# uc4h_airspeed_v020-wholes.net
KiCad netlist of a schematic drawn in EAGLE
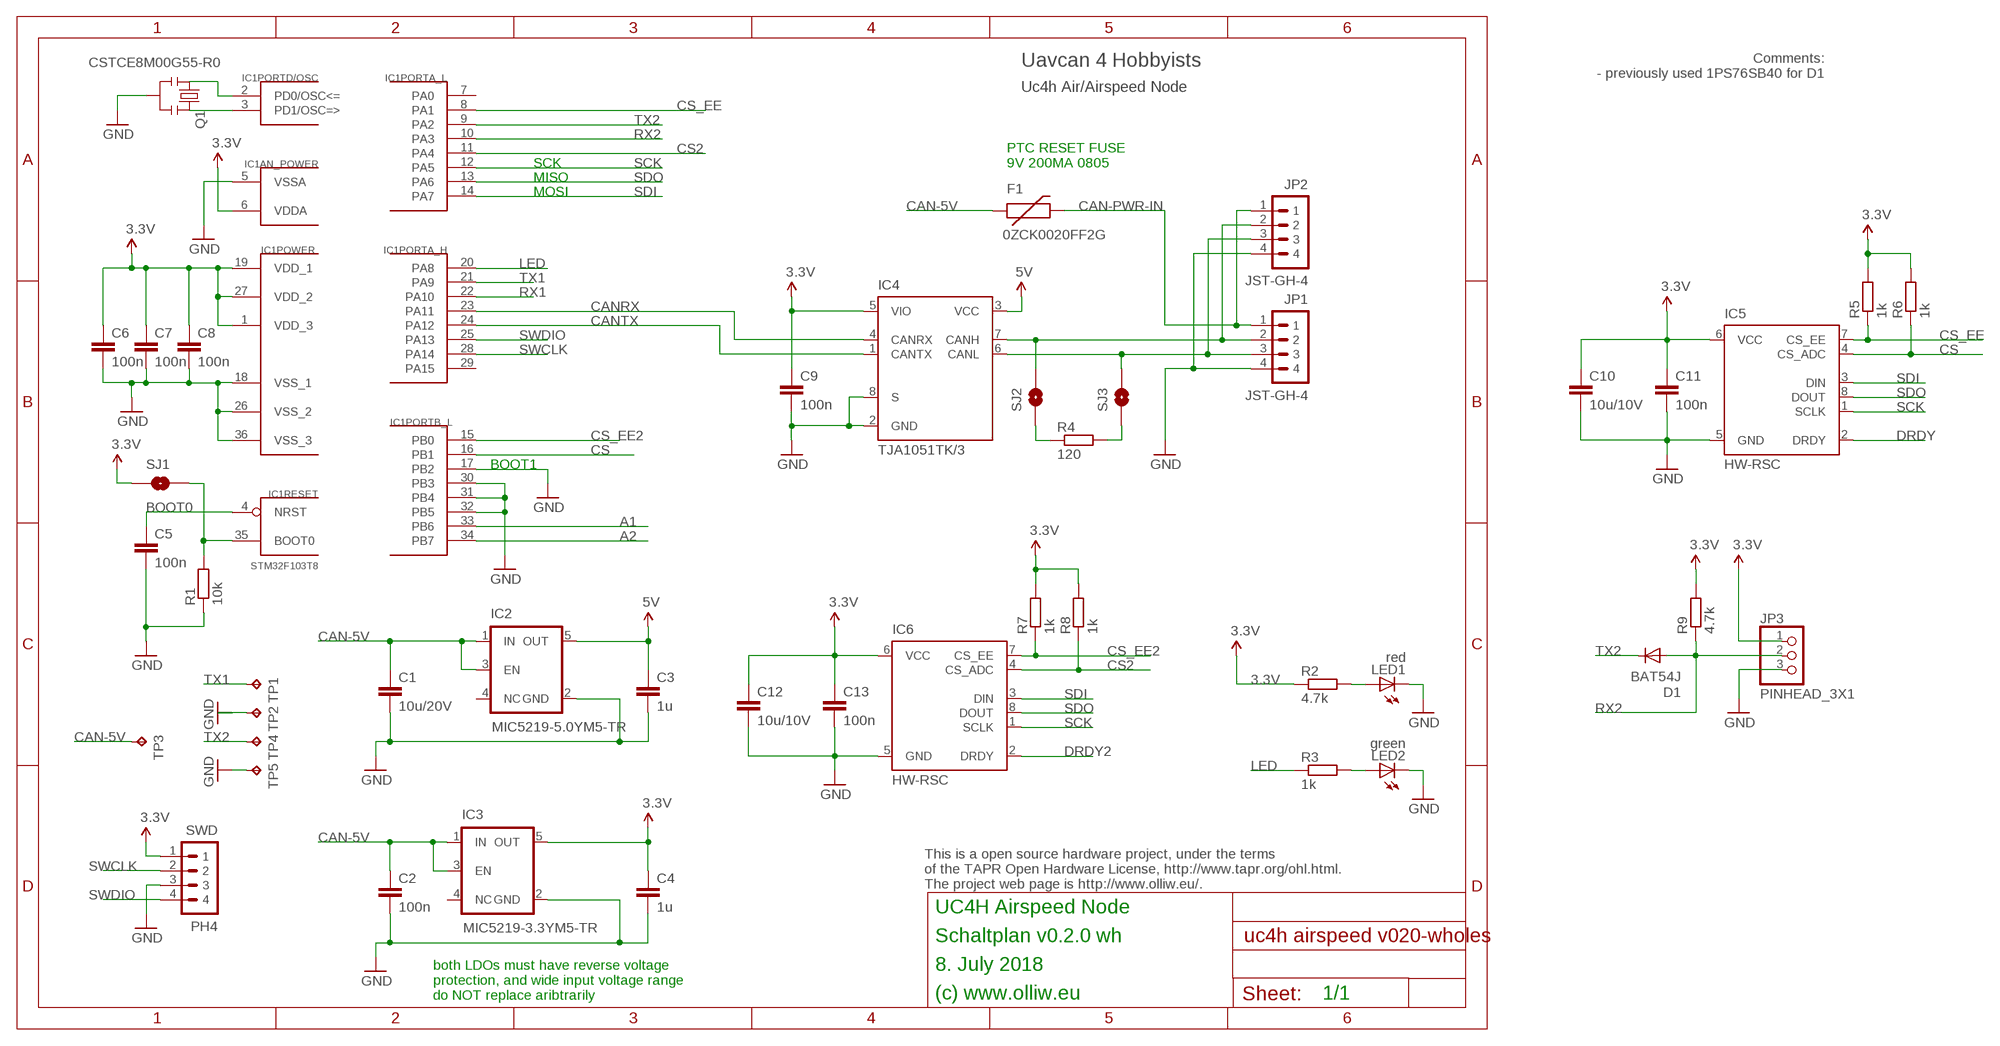
[diagram p0: schematic, sheet 1]

(export (version "E")
  (design (tool "Eeschema 10.0.6"))
  (components
    (comp (ref "C1")
      (value "10u/20V")
      (footprint "eagle-import:C1206")
      (libsource (lib "eagle-import") (part "C-EUC1206"))
    )
    (comp (ref "C2")
      (value "100n")
      (footprint "eagle-import:C0603K")
      (libsource (lib "eagle-import") (part "C-EUC0603K"))
    )
    (comp (ref "C3")
      (value "1u")
      (footprint "eagle-import:C0603K")
      (libsource (lib "eagle-import") (part "C-EUC0603K"))
    )
    (comp (ref "C4")
      (value "1u")
      (footprint "eagle-import:C0603K")
      (libsource (lib "eagle-import") (part "C-EUC0603K"))
    )
    (comp (ref "C5")
      (value "100n")
      (footprint "eagle-import:C0603K")
      (libsource (lib "eagle-import") (part "C-EUC0603K"))
    )
    (comp (ref "C6")
      (value "100n")
      (footprint "eagle-import:C0603K")
      (libsource (lib "eagle-import") (part "C-EUC0603K"))
    )
    (comp (ref "C7")
      (value "100n")
      (footprint "eagle-import:C0603K")
      (libsource (lib "eagle-import") (part "C-EUC0603K"))
    )
    (comp (ref "C8")
      (value "100n")
      (footprint "eagle-import:C0603K")
      (libsource (lib "eagle-import") (part "C-EUC0603K"))
    )
    (comp (ref "C9")
      (value "100n")
      (footprint "eagle-import:C0603K")
      (libsource (lib "eagle-import") (part "C-EUC0603K"))
    )
    (comp (ref "C10")
      (value "10u/10V")
      (footprint "eagle-import:C1206")
      (libsource (lib "eagle-import") (part "C-EUC1206"))
    )
    (comp (ref "C11")
      (value "100n")
      (footprint "eagle-import:C0603K")
      (libsource (lib "eagle-import") (part "C-EUC0603K"))
    )
    (comp (ref "C12")
      (value "10u/10V")
      (footprint "eagle-import:C1206")
      (libsource (lib "eagle-import") (part "C-EUC1206"))
    )
    (comp (ref "C13")
      (value "100n")
      (footprint "eagle-import:C0603K")
      (libsource (lib "eagle-import") (part "C-EUC0603K"))
    )
    (comp (ref "D1")
      (value "BAT54J")
      (footprint "eagle-import:SOD110-R")
      (libsource (lib "eagle-import") (part "DIODE-SOD110-R"))
    )
    (comp (ref "F1")
      (value "0ZCK0020FF2G")
      (footprint "eagle-import:FUSE-0805")
      (libsource (lib "eagle-import") (part "FUSE-PTCFUSE-0805"))
    )
    (comp (ref "IC1")
      (value "STM32F103T8")
      (footprint "eagle-import:VFQFPN36")
      (libsource (lib "eagle-import") (part "STM32F10XTXU6"))
    )
    (comp (ref "IC2")
      (value "MIC5219-5.0YM5-TR")
      (footprint "eagle-import:SOT23-5")
      (libsource (lib "eagle-import") (part "V_REG_TPS76433SOT23-5"))
    )
    (comp (ref "IC3")
      (value "MIC5219-3.3YM5-TR")
      (footprint "eagle-import:SOT23-5")
      (libsource (lib "eagle-import") (part "V_REG_TPS76433SOT23-5"))
    )
    (comp (ref "IC4")
      (value "TJA1051TK/3")
      (footprint "eagle-import:HVSON8")
      (libsource (lib "eagle-import") (part "TJA1051TK/3"))
    )
    (comp (ref "IC5")
      (value "HW-RSC")
      (footprint "eagle-import:HONEYWELL-8")
      (libsource (lib "eagle-import") (part "HW-RSC"))
    )
    (comp (ref "IC6")
      (value "HW-RSC")
      (footprint "eagle-import:HONEYWELL-8")
      (libsource (lib "eagle-import") (part "HW-RSC"))
    )
    (comp (ref "JP1")
      (value "JST-GH-4")
      (footprint "eagle-import:SM04B-GHS-TB")
      (libsource (lib "eagle-import") (part "JST-GH-4"))
    )
    (comp (ref "JP2")
      (value "JST-GH-4")
      (footprint "eagle-import:SM04B-GHS-TB")
      (libsource (lib "eagle-import") (part "JST-GH-4"))
    )
    (comp (ref "JP3")
      (value "PINHEAD_3X1")
      (footprint "eagle-import:PINHEAD_3X1")
      (libsource (lib "eagle-import") (part "PINHEAD_3X1"))
    )
    (comp (ref "LED1")
      (value "red")
      (footprint "eagle-import:CHIPLED_0603")
      (libsource (lib "eagle-import") (part "LEDCHIPLED_0603"))
    )
    (comp (ref "LED2")
      (value "green")
      (footprint "eagle-import:CHIPLED_0603")
      (libsource (lib "eagle-import") (part "LEDCHIPLED_0603"))
    )
    (comp (ref "Q1")
      (value "CSTCE8M00G55-R0")
      (footprint "eagle-import:RESONATOR-SMD")
      (libsource (lib "eagle-import") (part "RESONATORSMD"))
    )
    (comp (ref "R1")
      (value "10k")
      (footprint "eagle-import:R0603")
      (libsource (lib "eagle-import") (part "R-EU_R0603"))
    )
    (comp (ref "R2")
      (value "4.7k")
      (footprint "eagle-import:R0603")
      (libsource (lib "eagle-import") (part "R-EU_R0603"))
    )
    (comp (ref "R3")
      (value "1k")
      (footprint "eagle-import:R0603")
      (libsource (lib "eagle-import") (part "R-EU_R0603"))
    )
    (comp (ref "R4")
      (value "120")
      (footprint "eagle-import:R0603")
      (libsource (lib "eagle-import") (part "R-EU_R0603"))
    )
    (comp (ref "R5")
      (value "1k")
      (footprint "eagle-import:R0603")
      (libsource (lib "eagle-import") (part "R-EU_R0603"))
    )
    (comp (ref "R6")
      (value "1k")
      (footprint "eagle-import:R0603")
      (libsource (lib "eagle-import") (part "R-EU_R0603"))
    )
    (comp (ref "R7")
      (value "1k")
      (footprint "eagle-import:R0603")
      (libsource (lib "eagle-import") (part "R-EU_R0603"))
    )
    (comp (ref "R8")
      (value "1k")
      (footprint "eagle-import:R0603")
      (libsource (lib "eagle-import") (part "R-EU_R0603"))
    )
    (comp (ref "R9")
      (value "4.7k")
      (footprint "eagle-import:R0603")
      (libsource (lib "eagle-import") (part "R-EU_R0603"))
    )
    (comp (ref "SJ1")
      (value "BOOT0")
      (footprint "eagle-import:SJ_2S-NO")
      (libsource (lib "eagle-import") (part "SOLDERJUMPERNO"))
    )
    (comp (ref "SJ2")
      (value "SOLDERJUMPERNO")
      (footprint "eagle-import:SJ_2S-NO")
      (libsource (lib "eagle-import") (part "SOLDERJUMPERNO"))
    )
    (comp (ref "SJ3")
      (value "SOLDERJUMPERNO")
      (footprint "eagle-import:SJ_2S-NO")
      (libsource (lib "eagle-import") (part "SOLDERJUMPERNO"))
    )
    (comp (ref "SWD")
      (value "PH4")
      (footprint "eagle-import:4X1_1P27_OCT_BILEX")
      (libsource (lib "eagle-import") (part "P4X1_1P27-OCT_BILEX"))
    )
    (comp (ref "TP1")
      (value "TPB1,27")
      (footprint "eagle-import:B1,27")
      (libsource (lib "eagle-import") (part "TPB1,27"))
    )
    (comp (ref "TP2")
      (value "TPB1,27")
      (footprint "eagle-import:B1,27")
      (libsource (lib "eagle-import") (part "TPB1,27"))
    )
    (comp (ref "TP3")
      (value "TPB1,27")
      (footprint "eagle-import:B1,27")
      (libsource (lib "eagle-import") (part "TPB1,27"))
    )
    (comp (ref "TP4")
      (value "TPB1,27")
      (footprint "eagle-import:B1,27")
      (libsource (lib "eagle-import") (part "TPB1,27"))
    )
    (comp (ref "TP5")
      (value "TPB1,27")
      (footprint "eagle-import:B1,27")
      (libsource (lib "eagle-import") (part "TPB1,27"))
    )
  )
  (nets
    (net (code "1") (name "/A1") (class "Default")
      (node (ref "IC1") (pin "33") (pinfunction "PB6_33") (pintype "bidirectional"))
    )
    (net (code "2") (name "/A2") (class "Default")
      (node (ref "IC1") (pin "34") (pinfunction "PB7_34") (pintype "bidirectional"))
    )
    (net (code "3") (name "/CAN-5V") (class "Default")
      (node (ref "C1") (pin "1") (pinfunction "1_1") (pintype "passive"))
      (node (ref "C2") (pin "1") (pinfunction "1_1") (pintype "passive"))
      (node (ref "F1") (pin "1") (pinfunction "1_1") (pintype "bidirectional"))
      (node (ref "IC2") (pin "1") (pinfunction "IN_1") (pintype "power_in"))
      (node (ref "IC2") (pin "3") (pinfunction "EN_3") (pintype "input"))
      (node (ref "IC3") (pin "1") (pinfunction "IN_1") (pintype "power_in"))
      (node (ref "IC3") (pin "3") (pinfunction "EN_3") (pintype "input"))
      (node (ref "TP3") (pin "TP") (pinfunction "TP_TP") (pintype "input"))
    )
    (net (code "4") (name "/CAN-PWR-IN") (class "Default")
      (node (ref "F1") (pin "2") (pinfunction "2_2") (pintype "bidirectional"))
      (node (ref "JP1") (pin "1") (pinfunction "1_1") (pintype "passive"))
      (node (ref "JP2") (pin "1") (pinfunction "1_1") (pintype "passive"))
    )
    (net (code "5") (name "/CANRX") (class "Default")
      (node (ref "IC1") (pin "23") (pinfunction "PA11_23") (pintype "bidirectional"))
      (node (ref "IC4") (pin "4") (pinfunction "CANRX_4") (pintype "output"))
    )
    (net (code "6") (name "/CANTX") (class "Default")
      (node (ref "IC1") (pin "24") (pinfunction "PA12_24") (pintype "bidirectional"))
      (node (ref "IC4") (pin "1") (pinfunction "CANTX_1") (pintype "input"))
    )
    (net (code "7") (name "/CS") (class "Default")
      (node (ref "IC1") (pin "16") (pinfunction "PB1_16") (pintype "bidirectional"))
      (node (ref "IC5") (pin "4") (pinfunction "CS_ADC_4") (pintype "input"))
      (node (ref "R6") (pin "1") (pinfunction "1_1") (pintype "passive"))
    )
    (net (code "8") (name "/CS2") (class "Default")
      (node (ref "IC1") (pin "11") (pinfunction "PA4_11") (pintype "bidirectional"))
      (node (ref "IC6") (pin "4") (pinfunction "CS_ADC_4") (pintype "input"))
      (node (ref "R8") (pin "1") (pinfunction "1_1") (pintype "passive"))
    )
    (net (code "9") (name "/CS_EE") (class "Default")
      (node (ref "IC1") (pin "8") (pinfunction "PA1_8") (pintype "bidirectional"))
      (node (ref "IC5") (pin "7") (pinfunction "CS_EE_7") (pintype "input"))
      (node (ref "R5") (pin "1") (pinfunction "1_1") (pintype "passive"))
    )
    (net (code "10") (name "/CS_EE2") (class "Default")
      (node (ref "IC1") (pin "15") (pinfunction "PB0_15") (pintype "bidirectional"))
      (node (ref "IC6") (pin "7") (pinfunction "CS_EE_7") (pintype "input"))
      (node (ref "R7") (pin "1") (pinfunction "1_1") (pintype "passive"))
    )
    (net (code "11") (name "/DRDY") (class "Default")
      (node (ref "IC5") (pin "2") (pinfunction "DRDY_2") (pintype "output"))
    )
    (net (code "12") (name "/DRDY2") (class "Default")
      (node (ref "IC6") (pin "2") (pinfunction "DRDY_2") (pintype "output"))
    )
    (net (code "13") (name "/LED") (class "Default")
      (node (ref "IC1") (pin "20") (pinfunction "PA8_20") (pintype "bidirectional"))
      (node (ref "R3") (pin "1") (pinfunction "1_1") (pintype "passive"))
    )
    (net (code "14") (name "/RX1") (class "Default")
      (node (ref "IC1") (pin "22") (pinfunction "PA10_22") (pintype "bidirectional"))
    )
    (net (code "15") (name "/RX2") (class "Default")
      (node (ref "D1") (pin "A") (pinfunction "A_A") (pintype "passive"))
      (node (ref "IC1") (pin "10") (pinfunction "PA3_10") (pintype "bidirectional"))
      (node (ref "JP3") (pin "2") (pinfunction "3_2") (pintype "passive"))
      (node (ref "R9") (pin "1") (pinfunction "1_1") (pintype "passive"))
    )
    (net (code "16") (name "/SCK") (class "Default")
      (node (ref "IC1") (pin "12") (pinfunction "PA5_12") (pintype "bidirectional"))
      (node (ref "IC5") (pin "1") (pinfunction "SCLK_1") (pintype "input"))
      (node (ref "IC6") (pin "1") (pinfunction "SCLK_1") (pintype "input"))
    )
    (net (code "17") (name "/SDI") (class "Default")
      (node (ref "IC1") (pin "14") (pinfunction "PA7_14") (pintype "bidirectional"))
      (node (ref "IC5") (pin "3") (pinfunction "DIN_3") (pintype "input"))
      (node (ref "IC6") (pin "3") (pinfunction "DIN_3") (pintype "input"))
    )
    (net (code "18") (name "/SDO") (class "Default")
      (node (ref "IC1") (pin "13") (pinfunction "PA6_13") (pintype "bidirectional"))
      (node (ref "IC5") (pin "8") (pinfunction "DOUT_8") (pintype "output"))
      (node (ref "IC6") (pin "8") (pinfunction "DOUT_8") (pintype "output"))
    )
    (net (code "19") (name "/SWCLK") (class "Default")
      (node (ref "IC1") (pin "28") (pinfunction "PA14_28") (pintype "bidirectional"))
      (node (ref "SWD") (pin "2") (pinfunction "2_2") (pintype "passive"))
    )
    (net (code "20") (name "/SWDIO") (class "Default")
      (node (ref "IC1") (pin "25") (pinfunction "PA13_25") (pintype "bidirectional"))
      (node (ref "SWD") (pin "4") (pinfunction "4_4") (pintype "passive"))
    )
    (net (code "21") (name "/TX1") (class "Default")
      (node (ref "IC1") (pin "21") (pinfunction "PA9_21") (pintype "bidirectional"))
      (node (ref "TP1") (pin "TP") (pinfunction "TP_TP") (pintype "input"))
    )
    (net (code "22") (name "/TX2") (class "Default")
      (node (ref "D1") (pin "C") (pinfunction "C_C") (pintype "passive"))
      (node (ref "IC1") (pin "9") (pinfunction "PA2_9") (pintype "bidirectional"))
      (node (ref "TP4") (pin "TP") (pinfunction "TP_TP") (pintype "input"))
    )
    (net (code "23") (name "3.3V") (class "Default")
      (node (ref "C10") (pin "1") (pinfunction "1_1") (pintype "passive"))
      (node (ref "C11") (pin "1") (pinfunction "1_1") (pintype "passive"))
      (node (ref "C12") (pin "1") (pinfunction "1_1") (pintype "passive"))
      (node (ref "C13") (pin "1") (pinfunction "1_1") (pintype "passive"))
      (node (ref "C4") (pin "1") (pinfunction "1_1") (pintype "passive"))
      (node (ref "C6") (pin "1") (pinfunction "1_1") (pintype "passive"))
      (node (ref "C7") (pin "1") (pinfunction "1_1") (pintype "passive"))
      (node (ref "C8") (pin "1") (pinfunction "1_1") (pintype "passive"))
      (node (ref "C9") (pin "1") (pinfunction "1_1") (pintype "passive"))
      (node (ref "IC1") (pin "1") (pinfunction "VDD_3_1") (pintype "power_in"))
      (node (ref "IC1") (pin "19") (pinfunction "VDD_1_19") (pintype "power_in"))
      (node (ref "IC1") (pin "27") (pinfunction "VDD_2_27") (pintype "power_in"))
      (node (ref "IC1") (pin "6") (pinfunction "VDDA_6") (pintype "power_in"))
      (node (ref "IC3") (pin "5") (pinfunction "OUT_5") (pintype "output"))
      (node (ref "IC4") (pin "5") (pinfunction "VIO_5") (pintype "power_in"))
      (node (ref "IC5") (pin "6") (pinfunction "VCC_6") (pintype "power_in"))
      (node (ref "IC6") (pin "6") (pinfunction "VCC_6") (pintype "power_in"))
      (node (ref "JP3") (pin "1") (pinfunction "1_1") (pintype "passive"))
      (node (ref "R2") (pin "1") (pinfunction "1_1") (pintype "passive"))
      (node (ref "R5") (pin "2") (pinfunction "2_2") (pintype "passive"))
      (node (ref "R6") (pin "2") (pinfunction "2_2") (pintype "passive"))
      (node (ref "R7") (pin "2") (pinfunction "2_2") (pintype "passive"))
      (node (ref "R8") (pin "2") (pinfunction "2_2") (pintype "passive"))
      (node (ref "R9") (pin "2") (pinfunction "2_2") (pintype "passive"))
      (node (ref "SJ1") (pin "1") (pinfunction "1_1") (pintype "passive"))
      (node (ref "SWD") (pin "1") (pinfunction "1_1") (pintype "passive"))
    )
    (net (code "24") (name "5V") (class "Default")
      (node (ref "C3") (pin "1") (pinfunction "1_1") (pintype "passive"))
      (node (ref "IC2") (pin "5") (pinfunction "OUT_5") (pintype "output"))
      (node (ref "IC4") (pin "3") (pinfunction "VCC_3") (pintype "power_in"))
    )
    (net (code "25") (name "GND") (class "Default")
      (node (ref "C1") (pin "2") (pinfunction "2_2") (pintype "passive"))
      (node (ref "C10") (pin "2") (pinfunction "2_2") (pintype "passive"))
      (node (ref "C11") (pin "2") (pinfunction "2_2") (pintype "passive"))
      (node (ref "C12") (pin "2") (pinfunction "2_2") (pintype "passive"))
      (node (ref "C13") (pin "2") (pinfunction "2_2") (pintype "passive"))
      (node (ref "C2") (pin "2") (pinfunction "2_2") (pintype "passive"))
      (node (ref "C3") (pin "2") (pinfunction "2_2") (pintype "passive"))
      (node (ref "C4") (pin "2") (pinfunction "2_2") (pintype "passive"))
      (node (ref "C5") (pin "2") (pinfunction "2_2") (pintype "passive"))
      (node (ref "C6") (pin "2") (pinfunction "2_2") (pintype "passive"))
      (node (ref "C7") (pin "2") (pinfunction "2_2") (pintype "passive"))
      (node (ref "C8") (pin "2") (pinfunction "2_2") (pintype "passive"))
      (node (ref "C9") (pin "2") (pinfunction "2_2") (pintype "passive"))
      (node (ref "IC1") (pin "17") (pinfunction "PB2_17") (pintype "bidirectional"))
      (node (ref "IC1") (pin "18") (pinfunction "VSS_1_18") (pintype "power_in"))
      (node (ref "IC1") (pin "26") (pinfunction "VSS_2_26") (pintype "power_in"))
      (node (ref "IC1") (pin "30") (pinfunction "PB3_30") (pintype "bidirectional"))
      (node (ref "IC1") (pin "31") (pinfunction "PB4_31") (pintype "bidirectional"))
      (node (ref "IC1") (pin "32") (pinfunction "PB5_32") (pintype "bidirectional"))
      (node (ref "IC1") (pin "36") (pinfunction "VSS_3_36") (pintype "power_in"))
      (node (ref "IC1") (pin "5") (pinfunction "VSSA_5") (pintype "power_in"))
      (node (ref "IC2") (pin "2") (pinfunction "GND_2") (pintype "power_in"))
      (node (ref "IC3") (pin "2") (pinfunction "GND_2") (pintype "power_in"))
      (node (ref "IC4") (pin "2") (pinfunction "GND_2") (pintype "power_in"))
      (node (ref "IC4") (pin "8") (pinfunction "S_8") (pintype "input"))
      (node (ref "IC5") (pin "5") (pinfunction "GND_5") (pintype "power_in"))
      (node (ref "IC6") (pin "5") (pinfunction "GND_5") (pintype "power_in"))
      (node (ref "JP1") (pin "4") (pinfunction "4_4") (pintype "passive"))
      (node (ref "JP2") (pin "4") (pinfunction "4_4") (pintype "passive"))
      (node (ref "JP3") (pin "3") (pinfunction "5_3") (pintype "passive"))
      (node (ref "LED1") (pin "C") (pinfunction "C_C") (pintype "passive"))
      (node (ref "LED2") (pin "C") (pinfunction "C_C") (pintype "passive"))
      (node (ref "Q1") (pin "2") (pinfunction "2_2") (pintype "passive"))
      (node (ref "R1") (pin "1") (pinfunction "1_1") (pintype "passive"))
      (node (ref "SWD") (pin "3") (pinfunction "3_3") (pintype "passive"))
      (node (ref "TP2") (pin "TP") (pinfunction "TP_TP") (pintype "input"))
      (node (ref "TP5") (pin "TP") (pinfunction "TP_TP") (pintype "input"))
    )
    (net (code "26") (name "Net-(IC1E-PD0{slash}OSC<=)") (class "Default")
      (node (ref "IC1") (pin "2") (pinfunction "PD0/OSC<=_2") (pintype "bidirectional"))
      (node (ref "Q1") (pin "1") (pinfunction "1_1") (pintype "passive"))
    )
    (net (code "27") (name "Net-(IC1E-PD1{slash}OSC=>)") (class "Default")
      (node (ref "IC1") (pin "3") (pinfunction "PD1/OSC=>_3") (pintype "bidirectional"))
      (node (ref "Q1") (pin "3") (pinfunction "3_3") (pintype "passive"))
    )
    (net (code "28") (name "Net-(IC1G-BOOT0)") (class "Default")
      (node (ref "IC1") (pin "35") (pinfunction "BOOT0_35") (pintype "input"))
      (node (ref "R1") (pin "2") (pinfunction "2_2") (pintype "passive"))
      (node (ref "SJ1") (pin "2") (pinfunction "2_2") (pintype "passive"))
    )
    (net (code "29") (name "Net-(IC1G-NRST)") (class "Default")
      (node (ref "C5") (pin "1") (pinfunction "1_1") (pintype "passive"))
      (node (ref "IC1") (pin "4") (pinfunction "NRST_4") (pintype "input"))
    )
    (net (code "30") (name "Net-(IC4-CANH)") (class "Default")
      (node (ref "IC4") (pin "7") (pinfunction "CANH_7") (pintype "bidirectional"))
      (node (ref "JP1") (pin "2") (pinfunction "2_2") (pintype "passive"))
      (node (ref "JP2") (pin "2") (pinfunction "2_2") (pintype "passive"))
      (node (ref "SJ2") (pin "2") (pinfunction "2_2") (pintype "passive"))
    )
    (net (code "31") (name "Net-(IC4-CANL)") (class "Default")
      (node (ref "IC4") (pin "6") (pinfunction "CANL_6") (pintype "bidirectional"))
      (node (ref "JP1") (pin "3") (pinfunction "3_3") (pintype "passive"))
      (node (ref "JP2") (pin "3") (pinfunction "3_3") (pintype "passive"))
      (node (ref "SJ3") (pin "2") (pinfunction "2_2") (pintype "passive"))
    )
    (net (code "32") (name "Net-(LED1-PadA)") (class "Default")
      (node (ref "LED1") (pin "A") (pinfunction "A_A") (pintype "passive"))
      (node (ref "R2") (pin "2") (pinfunction "2_2") (pintype "passive"))
    )
    (net (code "33") (name "Net-(LED2-PadA)") (class "Default")
      (node (ref "LED2") (pin "A") (pinfunction "A_A") (pintype "passive"))
      (node (ref "R3") (pin "2") (pinfunction "2_2") (pintype "passive"))
    )
    (net (code "34") (name "Net-(R4-Pad1)") (class "Default")
      (node (ref "R4") (pin "1") (pinfunction "1_1") (pintype "passive"))
      (node (ref "SJ2") (pin "1") (pinfunction "1_1") (pintype "passive"))
    )
    (net (code "35") (name "Net-(R4-Pad2)") (class "Default")
      (node (ref "R4") (pin "2") (pinfunction "2_2") (pintype "passive"))
      (node (ref "SJ3") (pin "1") (pinfunction "1_1") (pintype "passive"))
    )
    (net (code "36") (name "unconnected-(IC1B-PA15-Pad29)") (class "Default")
      (node (ref "IC1") (pin "29") (pinfunction "PA15_29") (pintype "bidirectional"))
    )
    (net (code "37") (name "unconnected-(IC1C-PA0-Pad7)") (class "Default")
      (node (ref "IC1") (pin "7") (pinfunction "PA0_7") (pintype "bidirectional"))
    )
    (net (code "38") (name "unconnected-(IC2-NC-Pad4)") (class "Default")
      (node (ref "IC2") (pin "4") (pinfunction "NC_4") (pintype "passive"))
    )
    (net (code "39") (name "unconnected-(IC3-NC-Pad4)") (class "Default")
      (node (ref "IC3") (pin "4") (pinfunction "NC_4") (pintype "passive"))
    )
  )
)
